# ASD2009.net
KiCad netlist of a schematic drawn in EAGLE
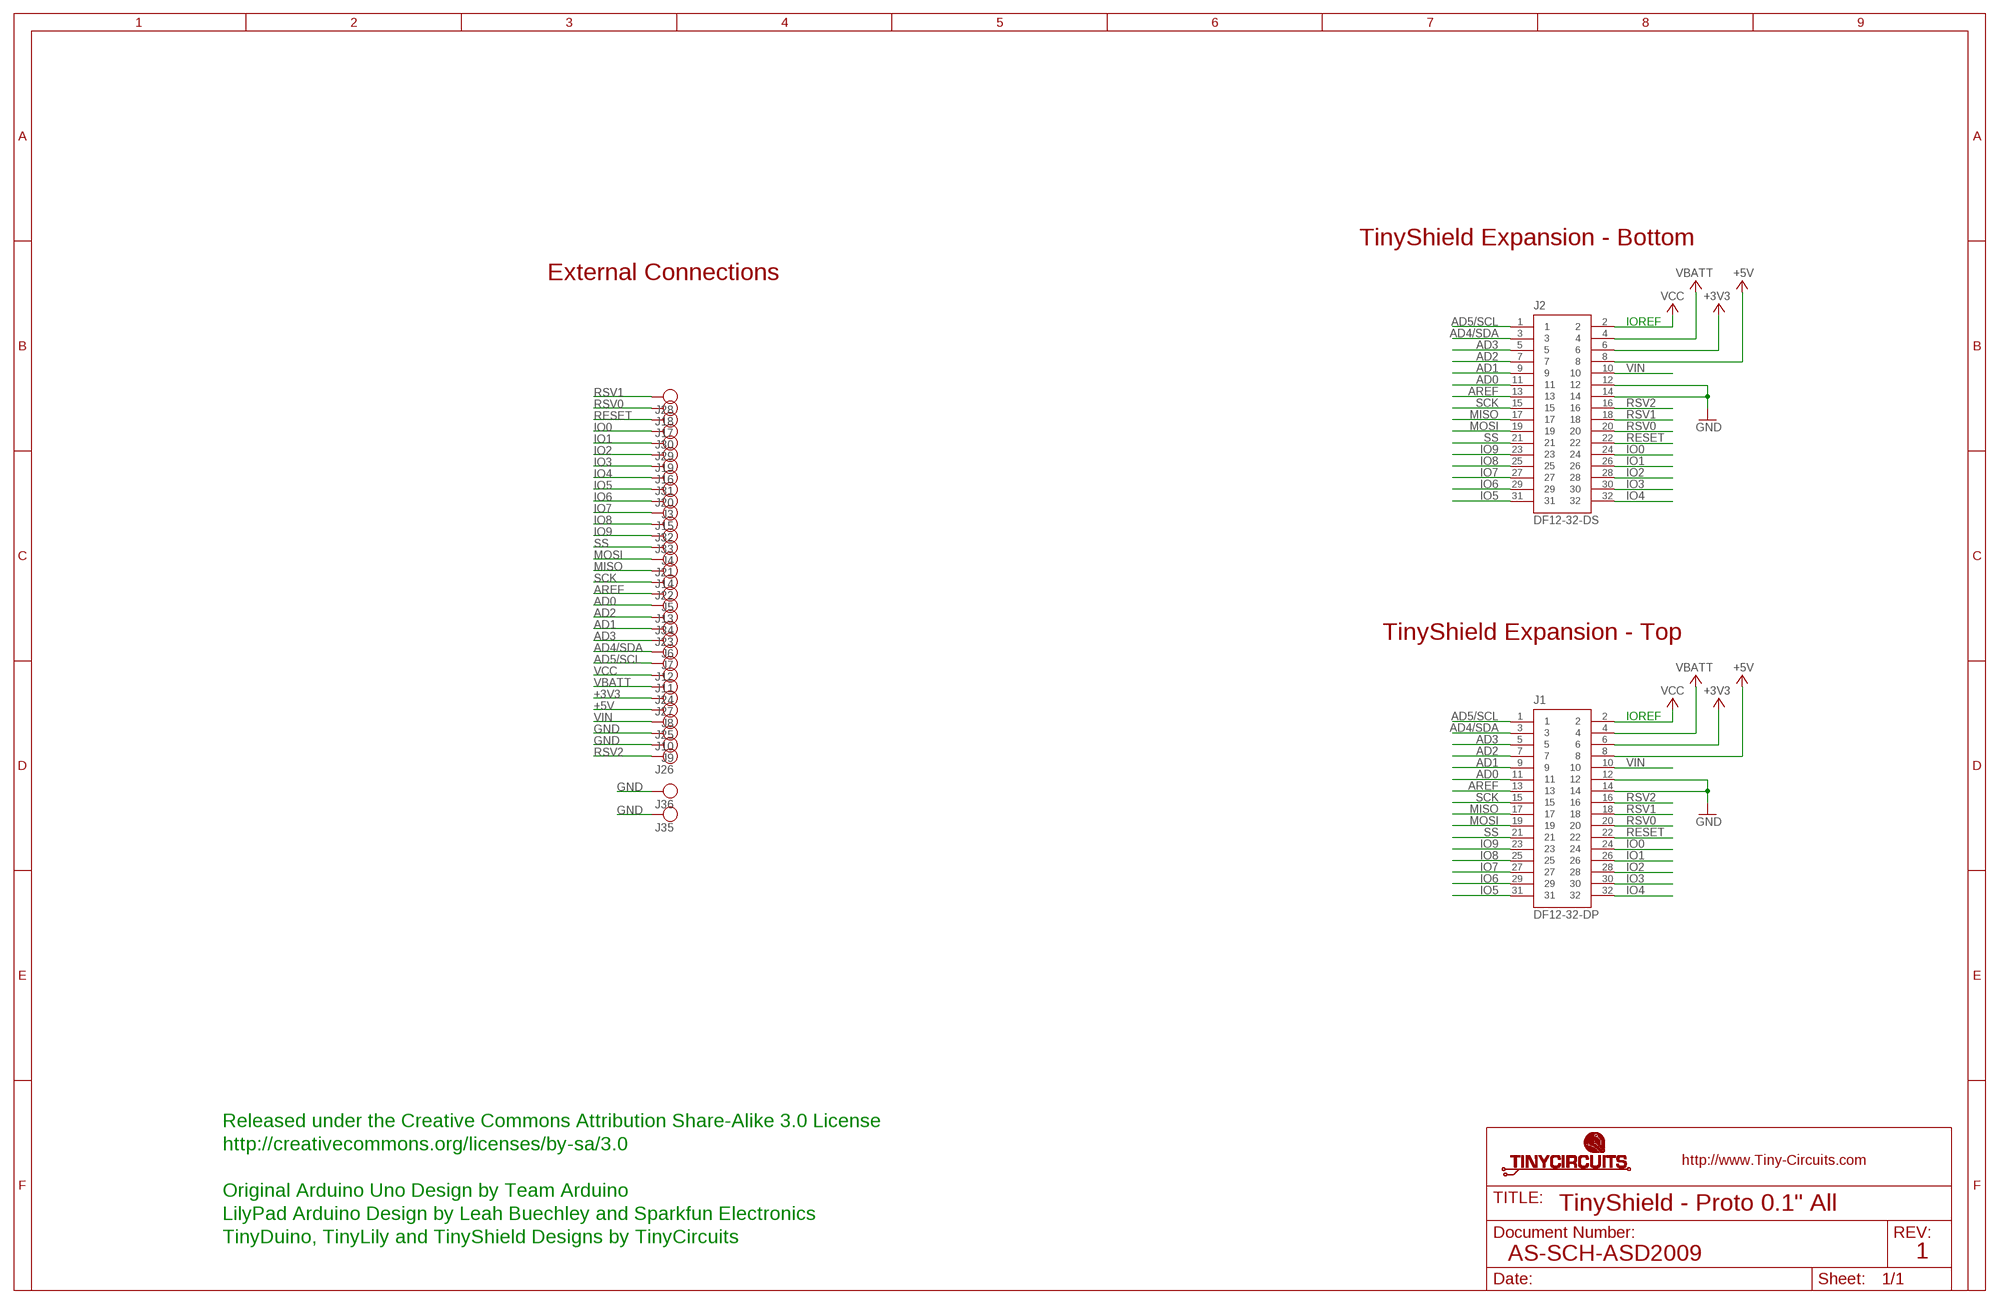
[diagram p0: schematic, sheet 1]

(export (version "E")
  (design (tool "Eeschema 10.0.6"))
  (components
    (comp (ref "J1")
      (value "DF12-32-DP")
      (footprint "eagle-import:DF12-32-DP")
      (fields (field (name "PARTNO") "AS-ITM-00015") (field (name "PARTNO_1") "AS-ITM-00015"))
      (libsource (lib "eagle-import") (part "AS-ITM-00015"))
    )
    (comp (ref "J2")
      (value "DF12-32-DS")
      (footprint "eagle-import:DF12-32-DS")
      (fields (field (name "PARTNO") "AS-ITM-00012") (field (name "PARTNO_1") "AS-ITM-00012"))
      (libsource (lib "eagle-import") (part "AS-ITM-00012"))
    )
    (comp (ref "J3")
      (value "PIN_1X.1\"1")
      (footprint "eagle-import:1X.1__2")
      (libsource (lib "eagle-import") (part "PIN_1X.1{dblquote}1"))
    )
    (comp (ref "J4")
      (value "PIN_1X.1\"1")
      (footprint "eagle-import:1X.1__2")
      (libsource (lib "eagle-import") (part "PIN_1X.1{dblquote}1"))
    )
    (comp (ref "J5")
      (value "PIN_1X.1\"1")
      (footprint "eagle-import:1X.1__2")
      (libsource (lib "eagle-import") (part "PIN_1X.1{dblquote}1"))
    )
    (comp (ref "J6")
      (value "PIN_1X.1\"1")
      (footprint "eagle-import:1X.1__2")
      (libsource (lib "eagle-import") (part "PIN_1X.1{dblquote}1"))
    )
    (comp (ref "J7")
      (value "PIN_1X.1\"1")
      (footprint "eagle-import:1X.1__2")
      (libsource (lib "eagle-import") (part "PIN_1X.1{dblquote}1"))
    )
    (comp (ref "J8")
      (value "PIN_1X.1\"1")
      (footprint "eagle-import:1X.1__2")
      (libsource (lib "eagle-import") (part "PIN_1X.1{dblquote}1"))
    )
    (comp (ref "J9")
      (value "PIN_1X.1\"1")
      (footprint "eagle-import:1X.1__2")
      (libsource (lib "eagle-import") (part "PIN_1X.1{dblquote}1"))
    )
    (comp (ref "J10")
      (value "PIN_1X.1\"1")
      (footprint "eagle-import:1X.1__2")
      (libsource (lib "eagle-import") (part "PIN_1X.1{dblquote}1"))
    )
    (comp (ref "J11")
      (value "PIN_1X.1\"1")
      (footprint "eagle-import:1X.1__2")
      (libsource (lib "eagle-import") (part "PIN_1X.1{dblquote}1"))
    )
    (comp (ref "J12")
      (value "PIN_1X.1\"1")
      (footprint "eagle-import:1X.1__2")
      (libsource (lib "eagle-import") (part "PIN_1X.1{dblquote}1"))
    )
    (comp (ref "J13")
      (value "PIN_1X.1\"1")
      (footprint "eagle-import:1X.1__2")
      (libsource (lib "eagle-import") (part "PIN_1X.1{dblquote}1"))
    )
    (comp (ref "J14")
      (value "PIN_1X.1\"1")
      (footprint "eagle-import:1X.1__2")
      (libsource (lib "eagle-import") (part "PIN_1X.1{dblquote}1"))
    )
    (comp (ref "J15")
      (value "PIN_1X.1\"1")
      (footprint "eagle-import:1X.1__2")
      (libsource (lib "eagle-import") (part "PIN_1X.1{dblquote}1"))
    )
    (comp (ref "J16")
      (value "PIN_1X.1\"1")
      (footprint "eagle-import:1X.1__2")
      (libsource (lib "eagle-import") (part "PIN_1X.1{dblquote}1"))
    )
    (comp (ref "J17")
      (value "PIN_1X.1\"1")
      (footprint "eagle-import:1X.1__2")
      (libsource (lib "eagle-import") (part "PIN_1X.1{dblquote}1"))
    )
    (comp (ref "J18")
      (value "PIN_1X.1\"1")
      (footprint "eagle-import:1X.1__2")
      (libsource (lib "eagle-import") (part "PIN_1X.1{dblquote}1"))
    )
    (comp (ref "J19")
      (value "PIN_1X.1\"1")
      (footprint "eagle-import:1X.1__2")
      (libsource (lib "eagle-import") (part "PIN_1X.1{dblquote}1"))
    )
    (comp (ref "J20")
      (value "PIN_1X.1\"1")
      (footprint "eagle-import:1X.1__2")
      (libsource (lib "eagle-import") (part "PIN_1X.1{dblquote}1"))
    )
    (comp (ref "J21")
      (value "PIN_1X.1\"1")
      (footprint "eagle-import:1X.1__2")
      (libsource (lib "eagle-import") (part "PIN_1X.1{dblquote}1"))
    )
    (comp (ref "J22")
      (value "PIN_1X.1\"1")
      (footprint "eagle-import:1X.1__2")
      (libsource (lib "eagle-import") (part "PIN_1X.1{dblquote}1"))
    )
    (comp (ref "J23")
      (value "PIN_1X.1\"1")
      (footprint "eagle-import:1X.1__2")
      (libsource (lib "eagle-import") (part "PIN_1X.1{dblquote}1"))
    )
    (comp (ref "J24")
      (value "PIN_1X.1\"1")
      (footprint "eagle-import:1X.1__2")
      (libsource (lib "eagle-import") (part "PIN_1X.1{dblquote}1"))
    )
    (comp (ref "J25")
      (value "PIN_1X.1\"1")
      (footprint "eagle-import:1X.1__2")
      (libsource (lib "eagle-import") (part "PIN_1X.1{dblquote}1"))
    )
    (comp (ref "J26")
      (value "PIN_1X.1\"1")
      (footprint "eagle-import:1X.1__2")
      (libsource (lib "eagle-import") (part "PIN_1X.1{dblquote}1"))
    )
    (comp (ref "J27")
      (value "PIN_1X.1\"1")
      (footprint "eagle-import:1X.1__2")
      (libsource (lib "eagle-import") (part "PIN_1X.1{dblquote}1"))
    )
    (comp (ref "J28")
      (value "PIN_1X.1\"1")
      (footprint "eagle-import:1X.1__2")
      (libsource (lib "eagle-import") (part "PIN_1X.1{dblquote}1"))
    )
    (comp (ref "J29")
      (value "PIN_1X.1\"1")
      (footprint "eagle-import:1X.1__2")
      (libsource (lib "eagle-import") (part "PIN_1X.1{dblquote}1"))
    )
    (comp (ref "J30")
      (value "PIN_1X.1\"1")
      (footprint "eagle-import:1X.1__2")
      (libsource (lib "eagle-import") (part "PIN_1X.1{dblquote}1"))
    )
    (comp (ref "J31")
      (value "PIN_1X.1\"1")
      (footprint "eagle-import:1X.1__2")
      (libsource (lib "eagle-import") (part "PIN_1X.1{dblquote}1"))
    )
    (comp (ref "J32")
      (value "PIN_1X.1\"1")
      (footprint "eagle-import:1X.1__2")
      (libsource (lib "eagle-import") (part "PIN_1X.1{dblquote}1"))
    )
    (comp (ref "J33")
      (value "PIN_1X.1\"1")
      (footprint "eagle-import:1X.1__2")
      (libsource (lib "eagle-import") (part "PIN_1X.1{dblquote}1"))
    )
    (comp (ref "J34")
      (value "PIN_1X.1\"1")
      (footprint "eagle-import:1X.1__2")
      (libsource (lib "eagle-import") (part "PIN_1X.1{dblquote}1"))
    )
    (comp (ref "J35")
      (value "PIN_1X.1\"1")
      (footprint "eagle-import:1X.1__2")
      (libsource (lib "eagle-import") (part "PIN_1X.1{dblquote}1"))
    )
    (comp (ref "J36")
      (value "PIN_1X.1\"1")
      (footprint "eagle-import:1X.1__2")
      (libsource (lib "eagle-import") (part "PIN_1X.1{dblquote}1"))
    )
  )
  (nets
    (net (code "1") (name "+3V3") (class "Default")
      (node (ref "J1") (pin "6") (pinfunction "6_6") (pintype "bidirectional"))
      (node (ref "J2") (pin "6") (pinfunction "6_6") (pintype "bidirectional"))
      (node (ref "J27") (pin "1") (pinfunction "1_1") (pintype "bidirectional"))
    )
    (net (code "2") (name "+5V") (class "Default")
      (node (ref "J1") (pin "8") (pinfunction "8_8") (pintype "bidirectional"))
      (node (ref "J2") (pin "8") (pinfunction "8_8") (pintype "bidirectional"))
      (node (ref "J8") (pin "1") (pinfunction "1_1") (pintype "bidirectional"))
    )
    (net (code "3") (name "/AD0") (class "Default")
      (node (ref "J1") (pin "11") (pinfunction "11_11") (pintype "bidirectional"))
      (node (ref "J13") (pin "1") (pinfunction "1_1") (pintype "bidirectional"))
      (node (ref "J2") (pin "11") (pinfunction "11_11") (pintype "bidirectional"))
    )
    (net (code "4") (name "/AD1") (class "Default")
      (node (ref "J1") (pin "9") (pinfunction "9_9") (pintype "bidirectional"))
      (node (ref "J2") (pin "9") (pinfunction "9_9") (pintype "bidirectional"))
      (node (ref "J23") (pin "1") (pinfunction "1_1") (pintype "bidirectional"))
    )
    (net (code "5") (name "/AD2") (class "Default")
      (node (ref "J1") (pin "7") (pinfunction "7_7") (pintype "bidirectional"))
      (node (ref "J2") (pin "7") (pinfunction "7_7") (pintype "bidirectional"))
      (node (ref "J34") (pin "1") (pinfunction "1_1") (pintype "bidirectional"))
    )
    (net (code "6") (name "/AD3") (class "Default")
      (node (ref "J1") (pin "5") (pinfunction "5_5") (pintype "bidirectional"))
      (node (ref "J2") (pin "5") (pinfunction "5_5") (pintype "bidirectional"))
      (node (ref "J6") (pin "1") (pinfunction "1_1") (pintype "bidirectional"))
    )
    (net (code "7") (name "/AD4{slash}SDA") (class "Default")
      (node (ref "J1") (pin "3") (pinfunction "3_3") (pintype "bidirectional"))
      (node (ref "J2") (pin "3") (pinfunction "3_3") (pintype "bidirectional"))
      (node (ref "J7") (pin "1") (pinfunction "1_1") (pintype "bidirectional"))
    )
    (net (code "8") (name "/AD5{slash}SCL") (class "Default")
      (node (ref "J1") (pin "1") (pinfunction "1_1") (pintype "bidirectional"))
      (node (ref "J12") (pin "1") (pinfunction "1_1") (pintype "bidirectional"))
      (node (ref "J2") (pin "1") (pinfunction "1_1") (pintype "bidirectional"))
    )
    (net (code "9") (name "/AREF") (class "Default")
      (node (ref "J1") (pin "13") (pinfunction "13_13") (pintype "bidirectional"))
      (node (ref "J2") (pin "13") (pinfunction "13_13") (pintype "bidirectional"))
      (node (ref "J5") (pin "1") (pinfunction "1_1") (pintype "bidirectional"))
    )
    (net (code "10") (name "/IO0") (class "Default")
      (node (ref "J1") (pin "24") (pinfunction "24_24") (pintype "bidirectional"))
      (node (ref "J2") (pin "24") (pinfunction "24_24") (pintype "bidirectional"))
      (node (ref "J30") (pin "1") (pinfunction "1_1") (pintype "bidirectional"))
    )
    (net (code "11") (name "/IO1") (class "Default")
      (node (ref "J1") (pin "26") (pinfunction "26_26") (pintype "bidirectional"))
      (node (ref "J2") (pin "26") (pinfunction "26_26") (pintype "bidirectional"))
      (node (ref "J29") (pin "1") (pinfunction "1_1") (pintype "bidirectional"))
    )
    (net (code "12") (name "/IO2") (class "Default")
      (node (ref "J1") (pin "28") (pinfunction "28_28") (pintype "bidirectional"))
      (node (ref "J19") (pin "1") (pinfunction "1_1") (pintype "bidirectional"))
      (node (ref "J2") (pin "28") (pinfunction "28_28") (pintype "bidirectional"))
    )
    (net (code "13") (name "/IO3") (class "Default")
      (node (ref "J1") (pin "30") (pinfunction "30_30") (pintype "bidirectional"))
      (node (ref "J16") (pin "1") (pinfunction "1_1") (pintype "bidirectional"))
      (node (ref "J2") (pin "30") (pinfunction "30_30") (pintype "bidirectional"))
    )
    (net (code "14") (name "/IO4") (class "Default")
      (node (ref "J1") (pin "32") (pinfunction "32_32") (pintype "bidirectional"))
      (node (ref "J2") (pin "32") (pinfunction "32_32") (pintype "bidirectional"))
      (node (ref "J31") (pin "1") (pinfunction "1_1") (pintype "bidirectional"))
    )
    (net (code "15") (name "/IO5") (class "Default")
      (node (ref "J1") (pin "31") (pinfunction "31_31") (pintype "bidirectional"))
      (node (ref "J2") (pin "31") (pinfunction "31_31") (pintype "bidirectional"))
      (node (ref "J20") (pin "1") (pinfunction "1_1") (pintype "bidirectional"))
    )
    (net (code "16") (name "/IO6") (class "Default")
      (node (ref "J1") (pin "29") (pinfunction "29_29") (pintype "bidirectional"))
      (node (ref "J2") (pin "29") (pinfunction "29_29") (pintype "bidirectional"))
      (node (ref "J3") (pin "1") (pinfunction "1_1") (pintype "bidirectional"))
    )
    (net (code "17") (name "/IO7") (class "Default")
      (node (ref "J1") (pin "27") (pinfunction "27_27") (pintype "bidirectional"))
      (node (ref "J15") (pin "1") (pinfunction "1_1") (pintype "bidirectional"))
      (node (ref "J2") (pin "27") (pinfunction "27_27") (pintype "bidirectional"))
    )
    (net (code "18") (name "/IO8") (class "Default")
      (node (ref "J1") (pin "25") (pinfunction "25_25") (pintype "bidirectional"))
      (node (ref "J2") (pin "25") (pinfunction "25_25") (pintype "bidirectional"))
      (node (ref "J32") (pin "1") (pinfunction "1_1") (pintype "bidirectional"))
    )
    (net (code "19") (name "/IO9") (class "Default")
      (node (ref "J1") (pin "23") (pinfunction "23_23") (pintype "bidirectional"))
      (node (ref "J2") (pin "23") (pinfunction "23_23") (pintype "bidirectional"))
      (node (ref "J33") (pin "1") (pinfunction "1_1") (pintype "bidirectional"))
    )
    (net (code "20") (name "/MISO") (class "Default")
      (node (ref "J1") (pin "17") (pinfunction "17_17") (pintype "bidirectional"))
      (node (ref "J14") (pin "1") (pinfunction "1_1") (pintype "bidirectional"))
      (node (ref "J2") (pin "17") (pinfunction "17_17") (pintype "bidirectional"))
    )
    (net (code "21") (name "/MOSI") (class "Default")
      (node (ref "J1") (pin "19") (pinfunction "19_19") (pintype "bidirectional"))
      (node (ref "J2") (pin "19") (pinfunction "19_19") (pintype "bidirectional"))
      (node (ref "J21") (pin "1") (pinfunction "1_1") (pintype "bidirectional"))
    )
    (net (code "22") (name "/RESET") (class "Default")
      (node (ref "J1") (pin "22") (pinfunction "22_22") (pintype "bidirectional"))
      (node (ref "J17") (pin "1") (pinfunction "1_1") (pintype "bidirectional"))
      (node (ref "J2") (pin "22") (pinfunction "22_22") (pintype "bidirectional"))
    )
    (net (code "23") (name "/RSV0") (class "Default")
      (node (ref "J1") (pin "20") (pinfunction "20_20") (pintype "bidirectional"))
      (node (ref "J18") (pin "1") (pinfunction "1_1") (pintype "bidirectional"))
      (node (ref "J2") (pin "20") (pinfunction "20_20") (pintype "bidirectional"))
    )
    (net (code "24") (name "/RSV1") (class "Default")
      (node (ref "J1") (pin "18") (pinfunction "18_18") (pintype "bidirectional"))
      (node (ref "J2") (pin "18") (pinfunction "18_18") (pintype "bidirectional"))
      (node (ref "J28") (pin "1") (pinfunction "1_1") (pintype "bidirectional"))
    )
    (net (code "25") (name "/RSV2") (class "Default")
      (node (ref "J1") (pin "16") (pinfunction "16_16") (pintype "bidirectional"))
      (node (ref "J2") (pin "16") (pinfunction "16_16") (pintype "bidirectional"))
      (node (ref "J26") (pin "1") (pinfunction "1_1") (pintype "bidirectional"))
    )
    (net (code "26") (name "/SCK") (class "Default")
      (node (ref "J1") (pin "15") (pinfunction "15_15") (pintype "bidirectional"))
      (node (ref "J2") (pin "15") (pinfunction "15_15") (pintype "bidirectional"))
      (node (ref "J22") (pin "1") (pinfunction "1_1") (pintype "bidirectional"))
    )
    (net (code "27") (name "/SS") (class "Default")
      (node (ref "J1") (pin "21") (pinfunction "21_21") (pintype "bidirectional"))
      (node (ref "J2") (pin "21") (pinfunction "21_21") (pintype "bidirectional"))
      (node (ref "J4") (pin "1") (pinfunction "1_1") (pintype "bidirectional"))
    )
    (net (code "28") (name "/VIN") (class "Default")
      (node (ref "J1") (pin "10") (pinfunction "10_10") (pintype "bidirectional"))
      (node (ref "J2") (pin "10") (pinfunction "10_10") (pintype "bidirectional"))
      (node (ref "J25") (pin "1") (pinfunction "1_1") (pintype "bidirectional"))
    )
    (net (code "29") (name "GND") (class "Default")
      (node (ref "J1") (pin "12") (pinfunction "12_12") (pintype "bidirectional"))
      (node (ref "J1") (pin "14") (pinfunction "14_14") (pintype "bidirectional"))
      (node (ref "J10") (pin "1") (pinfunction "1_1") (pintype "bidirectional"))
      (node (ref "J2") (pin "12") (pinfunction "12_12") (pintype "bidirectional"))
      (node (ref "J2") (pin "14") (pinfunction "14_14") (pintype "bidirectional"))
      (node (ref "J35") (pin "1") (pinfunction "1_1") (pintype "bidirectional"))
      (node (ref "J36") (pin "1") (pinfunction "1_1") (pintype "bidirectional"))
      (node (ref "J9") (pin "1") (pinfunction "1_1") (pintype "bidirectional"))
    )
    (net (code "30") (name "VBATT") (class "Default")
      (node (ref "J1") (pin "4") (pinfunction "4_4") (pintype "bidirectional"))
      (node (ref "J2") (pin "4") (pinfunction "4_4") (pintype "bidirectional"))
      (node (ref "J24") (pin "1") (pinfunction "1_1") (pintype "bidirectional"))
    )
    (net (code "31") (name "VCC") (class "Default")
      (node (ref "J1") (pin "2") (pinfunction "2_2") (pintype "bidirectional"))
      (node (ref "J11") (pin "1") (pinfunction "1_1") (pintype "bidirectional"))
      (node (ref "J2") (pin "2") (pinfunction "2_2") (pintype "bidirectional"))
    )
  )
)
